# MacroPadTouch-ESP32.net
KiCad netlist of a schematic drawn in EasyEDA Pro
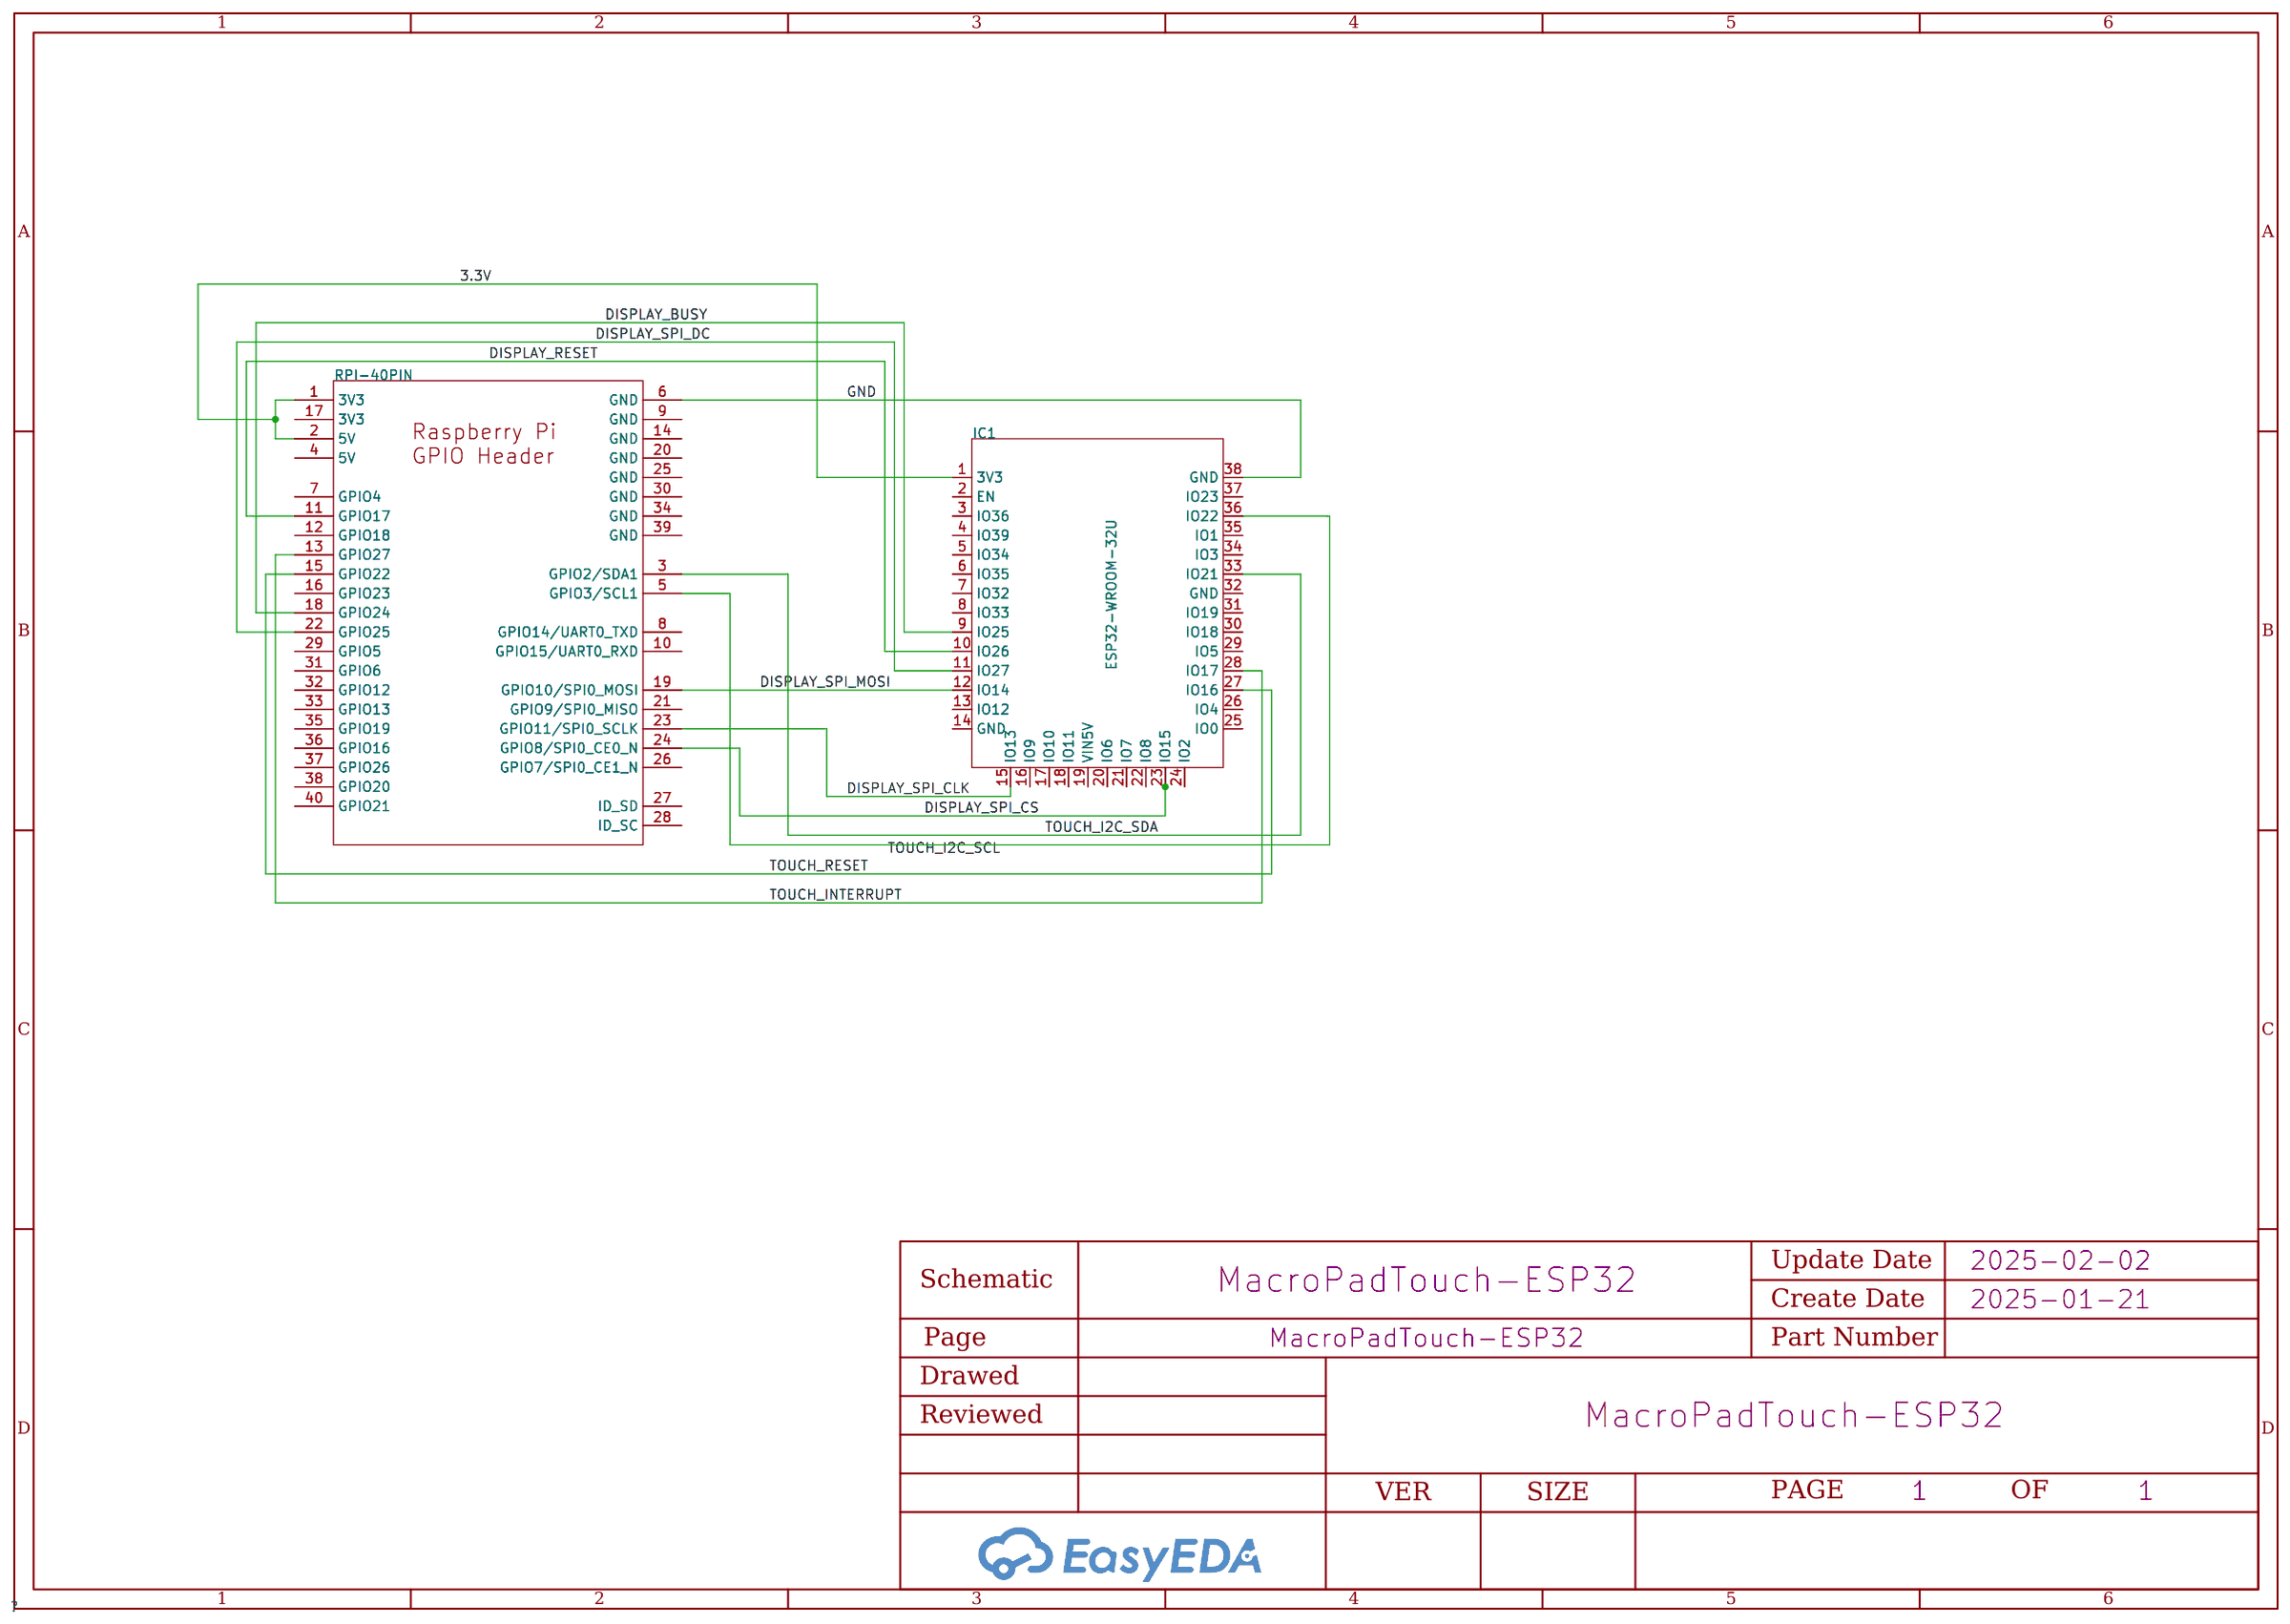
[diagram p0: schematic sheet]

(export (version "E")
  (design (tool "Eeschema 10.0.6"))
  (components
    (comp (ref "IC1")
      (value "ESP32-WROOM-32U")
      (footprint "easyedapro:ESP32-WROOM-32U")
      (libsource (lib "easyedapro") (part "ESP32-WROOM-32U"))
    )
    (comp (ref "RPI-40PIN")
      (value "~")
      (footprint "easyedapro:RASPBERRY_PI_GPIO_HEADER")
      (description "RPI 40pin connector schematic and headder")
      (libsource (lib "easyedapro") (part "Raspberry Pi GPIO Header"))
    )
  )
  (nets
    (net (code "1") (name "/3.3V") (class "Default")
      (node (ref "IC1") (pin "1") (pinfunction "3V3_1") (pintype "input"))
      (node (ref "RPI-40PIN") (pin "1") (pinfunction "3V3_1") (pintype "unspecified"))
      (node (ref "RPI-40PIN") (pin "2") (pinfunction "5V_2") (pintype "unspecified"))
    )
    (net (code "2") (name "/DISPLAY_BUSY") (class "Default")
      (node (ref "IC1") (pin "9") (pinfunction "IO25_9") (pintype "input"))
      (node (ref "RPI-40PIN") (pin "18") (pinfunction "GPIO24_18") (pintype "unspecified"))
    )
    (net (code "3") (name "/DISPLAY_RESET") (class "Default")
      (node (ref "IC1") (pin "10") (pinfunction "IO26_10") (pintype "input"))
      (node (ref "RPI-40PIN") (pin "11") (pinfunction "GPIO17_11") (pintype "unspecified"))
    )
    (net (code "4") (name "/DISPLAY_SPI_CLK") (class "Default")
      (node (ref "IC1") (pin "15") (pinfunction "IO13_15") (pintype "input"))
      (node (ref "RPI-40PIN") (pin "23") (pinfunction "GPIO11/SPI0_SCLK_23") (pintype "unspecified"))
    )
    (net (code "5") (name "/DISPLAY_SPI_CS") (class "Default")
      (node (ref "IC1") (pin "23") (pinfunction "IO15_23") (pintype "input"))
      (node (ref "RPI-40PIN") (pin "24") (pinfunction "GPIO8/SPI0_CE0_N_24") (pintype "unspecified"))
    )
    (net (code "6") (name "/DISPLAY_SPI_DC") (class "Default")
      (node (ref "IC1") (pin "11") (pinfunction "IO27_11") (pintype "input"))
      (node (ref "RPI-40PIN") (pin "22") (pinfunction "GPIO25_22") (pintype "unspecified"))
    )
    (net (code "7") (name "/DISPLAY_SPI_MOSI") (class "Default")
      (node (ref "IC1") (pin "12") (pinfunction "IO14_12") (pintype "input"))
      (node (ref "RPI-40PIN") (pin "19") (pinfunction "GPIO10/SPI0_MOSI_19") (pintype "unspecified"))
    )
    (net (code "8") (name "/GND") (class "Default")
      (node (ref "IC1") (pin "38") (pinfunction "GND_38") (pintype "input"))
      (node (ref "RPI-40PIN") (pin "6") (pinfunction "GND_6") (pintype "unspecified"))
    )
    (net (code "9") (name "/TOUCH_I2C_SCL") (class "Default")
      (node (ref "IC1") (pin "36") (pinfunction "IO22_36") (pintype "input"))
      (node (ref "RPI-40PIN") (pin "5") (pinfunction "GPIO3/SCL1_5") (pintype "unspecified"))
    )
    (net (code "10") (name "/TOUCH_I2C_SDA") (class "Default")
      (node (ref "IC1") (pin "33") (pinfunction "IO21_33") (pintype "input"))
      (node (ref "RPI-40PIN") (pin "3") (pinfunction "GPIO2/SDA1_3") (pintype "unspecified"))
    )
    (net (code "11") (name "/TOUCH_INTERRUPT") (class "Default")
      (node (ref "IC1") (pin "28") (pinfunction "IO17_28") (pintype "input"))
      (node (ref "RPI-40PIN") (pin "13") (pinfunction "GPIO27_13") (pintype "unspecified"))
    )
    (net (code "12") (name "/TOUCH_RESET") (class "Default")
      (node (ref "IC1") (pin "27") (pinfunction "IO16_27") (pintype "input"))
      (node (ref "RPI-40PIN") (pin "15") (pinfunction "GPIO22_15") (pintype "unspecified"))
    )
    (net (code "13") (name "unconnected-(IC1-EN-Pad2)") (class "Default")
      (node (ref "IC1") (pin "2") (pinfunction "EN_2") (pintype "input"))
    )
    (net (code "14") (name "unconnected-(IC1-GND-Pad14)") (class "Default")
      (node (ref "IC1") (pin "14") (pinfunction "GND_14") (pintype "input"))
    )
    (net (code "15") (name "unconnected-(IC1-GND-Pad32)") (class "Default")
      (node (ref "IC1") (pin "32") (pinfunction "GND_32") (pintype "input"))
    )
    (net (code "16") (name "unconnected-(IC1-IO0-Pad25)") (class "Default")
      (node (ref "IC1") (pin "25") (pinfunction "IO0_25") (pintype "input"))
    )
    (net (code "17") (name "unconnected-(IC1-IO1-Pad35)") (class "Default")
      (node (ref "IC1") (pin "35") (pinfunction "IO1_35") (pintype "input"))
    )
    (net (code "18") (name "unconnected-(IC1-IO2-Pad24)") (class "Default")
      (node (ref "IC1") (pin "24") (pinfunction "IO2_24") (pintype "input"))
    )
    (net (code "19") (name "unconnected-(IC1-IO3-Pad34)") (class "Default")
      (node (ref "IC1") (pin "34") (pinfunction "IO3_34") (pintype "input"))
    )
    (net (code "20") (name "unconnected-(IC1-IO4-Pad26)") (class "Default")
      (node (ref "IC1") (pin "26") (pinfunction "IO4_26") (pintype "input"))
    )
    (net (code "21") (name "unconnected-(IC1-IO5-Pad29)") (class "Default")
      (node (ref "IC1") (pin "29") (pinfunction "IO5_29") (pintype "input"))
    )
    (net (code "22") (name "unconnected-(IC1-IO6-Pad20)") (class "Default")
      (node (ref "IC1") (pin "20") (pinfunction "IO6_20") (pintype "input"))
    )
    (net (code "23") (name "unconnected-(IC1-IO7-Pad21)") (class "Default")
      (node (ref "IC1") (pin "21") (pinfunction "IO7_21") (pintype "input"))
    )
    (net (code "24") (name "unconnected-(IC1-IO8-Pad22)") (class "Default")
      (node (ref "IC1") (pin "22") (pinfunction "IO8_22") (pintype "input"))
    )
    (net (code "25") (name "unconnected-(IC1-IO9-Pad16)") (class "Default")
      (node (ref "IC1") (pin "16") (pinfunction "IO9_16") (pintype "input"))
    )
    (net (code "26") (name "unconnected-(IC1-IO10-Pad17)") (class "Default")
      (node (ref "IC1") (pin "17") (pinfunction "IO10_17") (pintype "input"))
    )
    (net (code "27") (name "unconnected-(IC1-IO11-Pad18)") (class "Default")
      (node (ref "IC1") (pin "18") (pinfunction "IO11_18") (pintype "input"))
    )
    (net (code "28") (name "unconnected-(IC1-IO12-Pad13)") (class "Default")
      (node (ref "IC1") (pin "13") (pinfunction "IO12_13") (pintype "input"))
    )
    (net (code "29") (name "unconnected-(IC1-IO18-Pad30)") (class "Default")
      (node (ref "IC1") (pin "30") (pinfunction "IO18_30") (pintype "input"))
    )
    (net (code "30") (name "unconnected-(IC1-IO19-Pad31)") (class "Default")
      (node (ref "IC1") (pin "31") (pinfunction "IO19_31") (pintype "input"))
    )
    (net (code "31") (name "unconnected-(IC1-IO23-Pad37)") (class "Default")
      (node (ref "IC1") (pin "37") (pinfunction "IO23_37") (pintype "input"))
    )
    (net (code "32") (name "unconnected-(IC1-IO32-Pad7)") (class "Default")
      (node (ref "IC1") (pin "7") (pinfunction "IO32_7") (pintype "input"))
    )
    (net (code "33") (name "unconnected-(IC1-IO33-Pad8)") (class "Default")
      (node (ref "IC1") (pin "8") (pinfunction "IO33_8") (pintype "input"))
    )
    (net (code "34") (name "unconnected-(IC1-IO34-Pad5)") (class "Default")
      (node (ref "IC1") (pin "5") (pinfunction "IO34_5") (pintype "input"))
    )
    (net (code "35") (name "unconnected-(IC1-IO35-Pad6)") (class "Default")
      (node (ref "IC1") (pin "6") (pinfunction "IO35_6") (pintype "input"))
    )
    (net (code "36") (name "unconnected-(IC1-IO36-Pad3)") (class "Default")
      (node (ref "IC1") (pin "3") (pinfunction "IO36_3") (pintype "input"))
    )
    (net (code "37") (name "unconnected-(IC1-IO39-Pad4)") (class "Default")
      (node (ref "IC1") (pin "4") (pinfunction "IO39_4") (pintype "input"))
    )
    (net (code "38") (name "unconnected-(IC1-VIN5V-Pad19)") (class "Default")
      (node (ref "IC1") (pin "19") (pinfunction "VIN5V_19") (pintype "input"))
    )
    (net (code "39") (name "unconnected-(RPI-40PIN-3V3-Pad17)") (class "Default")
      (node (ref "RPI-40PIN") (pin "17") (pinfunction "3V3_17") (pintype "unspecified"))
    )
    (net (code "40") (name "unconnected-(RPI-40PIN-5V-Pad4)") (class "Default")
      (node (ref "RPI-40PIN") (pin "4") (pinfunction "5V_4") (pintype "unspecified"))
    )
    (net (code "41") (name "unconnected-(RPI-40PIN-GND-Pad9)") (class "Default")
      (node (ref "RPI-40PIN") (pin "9") (pinfunction "GND_9") (pintype "unspecified"))
    )
    (net (code "42") (name "unconnected-(RPI-40PIN-GND-Pad14)") (class "Default")
      (node (ref "RPI-40PIN") (pin "14") (pinfunction "GND_14") (pintype "unspecified"))
    )
    (net (code "43") (name "unconnected-(RPI-40PIN-GND-Pad20)") (class "Default")
      (node (ref "RPI-40PIN") (pin "20") (pinfunction "GND_20") (pintype "unspecified"))
    )
    (net (code "44") (name "unconnected-(RPI-40PIN-GND-Pad25)") (class "Default")
      (node (ref "RPI-40PIN") (pin "25") (pinfunction "GND_25") (pintype "unspecified"))
    )
    (net (code "45") (name "unconnected-(RPI-40PIN-GND-Pad30)") (class "Default")
      (node (ref "RPI-40PIN") (pin "30") (pinfunction "GND_30") (pintype "unspecified"))
    )
    (net (code "46") (name "unconnected-(RPI-40PIN-GND-Pad34)") (class "Default")
      (node (ref "RPI-40PIN") (pin "34") (pinfunction "GND_34") (pintype "unspecified"))
    )
    (net (code "47") (name "unconnected-(RPI-40PIN-GND-Pad39)") (class "Default")
      (node (ref "RPI-40PIN") (pin "39") (pinfunction "GND_39") (pintype "unspecified"))
    )
    (net (code "48") (name "unconnected-(RPI-40PIN-GPIO4-Pad7)") (class "Default")
      (node (ref "RPI-40PIN") (pin "7") (pinfunction "GPIO4_7") (pintype "unspecified"))
    )
    (net (code "49") (name "unconnected-(RPI-40PIN-GPIO5-Pad29)") (class "Default")
      (node (ref "RPI-40PIN") (pin "29") (pinfunction "GPIO5_29") (pintype "unspecified"))
    )
    (net (code "50") (name "unconnected-(RPI-40PIN-GPIO6-Pad31)") (class "Default")
      (node (ref "RPI-40PIN") (pin "31") (pinfunction "GPIO6_31") (pintype "unspecified"))
    )
    (net (code "51") (name "unconnected-(RPI-40PIN-GPIO7{slash}SPI0_CE1_N-Pad26)") (class "Default")
      (node (ref "RPI-40PIN") (pin "26") (pinfunction "GPIO7/SPI0_CE1_N_26") (pintype "unspecified"))
    )
    (net (code "52") (name "unconnected-(RPI-40PIN-GPIO9{slash}SPI0_MISO-Pad21)") (class "Default")
      (node (ref "RPI-40PIN") (pin "21") (pinfunction "GPIO9/SPI0_MISO_21") (pintype "unspecified"))
    )
    (net (code "53") (name "unconnected-(RPI-40PIN-GPIO12-Pad32)") (class "Default")
      (node (ref "RPI-40PIN") (pin "32") (pinfunction "GPIO12_32") (pintype "unspecified"))
    )
    (net (code "54") (name "unconnected-(RPI-40PIN-GPIO13-Pad33)") (class "Default")
      (node (ref "RPI-40PIN") (pin "33") (pinfunction "GPIO13_33") (pintype "unspecified"))
    )
    (net (code "55") (name "unconnected-(RPI-40PIN-GPIO14{slash}UART0_TXD-Pad8)") (class "Default")
      (node (ref "RPI-40PIN") (pin "8") (pinfunction "GPIO14/UART0_TXD_8") (pintype "unspecified"))
    )
    (net (code "56") (name "unconnected-(RPI-40PIN-GPIO15{slash}UART0_RXD-Pad10)") (class "Default")
      (node (ref "RPI-40PIN") (pin "10") (pinfunction "GPIO15/UART0_RXD_10") (pintype "unspecified"))
    )
    (net (code "57") (name "unconnected-(RPI-40PIN-GPIO16-Pad36)") (class "Default")
      (node (ref "RPI-40PIN") (pin "36") (pinfunction "GPIO16_36") (pintype "unspecified"))
    )
    (net (code "58") (name "unconnected-(RPI-40PIN-GPIO18-Pad12)") (class "Default")
      (node (ref "RPI-40PIN") (pin "12") (pinfunction "GPIO18_12") (pintype "unspecified"))
    )
    (net (code "59") (name "unconnected-(RPI-40PIN-GPIO19-Pad35)") (class "Default")
      (node (ref "RPI-40PIN") (pin "35") (pinfunction "GPIO19_35") (pintype "unspecified"))
    )
    (net (code "60") (name "unconnected-(RPI-40PIN-GPIO20-Pad38)") (class "Default")
      (node (ref "RPI-40PIN") (pin "38") (pinfunction "GPIO20_38") (pintype "unspecified"))
    )
    (net (code "61") (name "unconnected-(RPI-40PIN-GPIO21-Pad40)") (class "Default")
      (node (ref "RPI-40PIN") (pin "40") (pinfunction "GPIO21_40") (pintype "unspecified"))
    )
    (net (code "62") (name "unconnected-(RPI-40PIN-GPIO23-Pad16)") (class "Default")
      (node (ref "RPI-40PIN") (pin "16") (pinfunction "GPIO23_16") (pintype "unspecified"))
    )
    (net (code "63") (name "unconnected-(RPI-40PIN-GPIO26-Pad37)") (class "Default")
      (node (ref "RPI-40PIN") (pin "37") (pinfunction "GPIO26_37") (pintype "unspecified"))
    )
    (net (code "64") (name "unconnected-(RPI-40PIN-ID_SC-Pad28)") (class "Default")
      (node (ref "RPI-40PIN") (pin "28") (pinfunction "ID_SC_28") (pintype "unspecified"))
    )
    (net (code "65") (name "unconnected-(RPI-40PIN-ID_SD-Pad27)") (class "Default")
      (node (ref "RPI-40PIN") (pin "27") (pinfunction "ID_SD_27") (pintype "unspecified"))
    )
  )
)
